# BDCMC_H-Bridge_24V50A.net
KiCad netlist of a schematic drawn in EAGLE
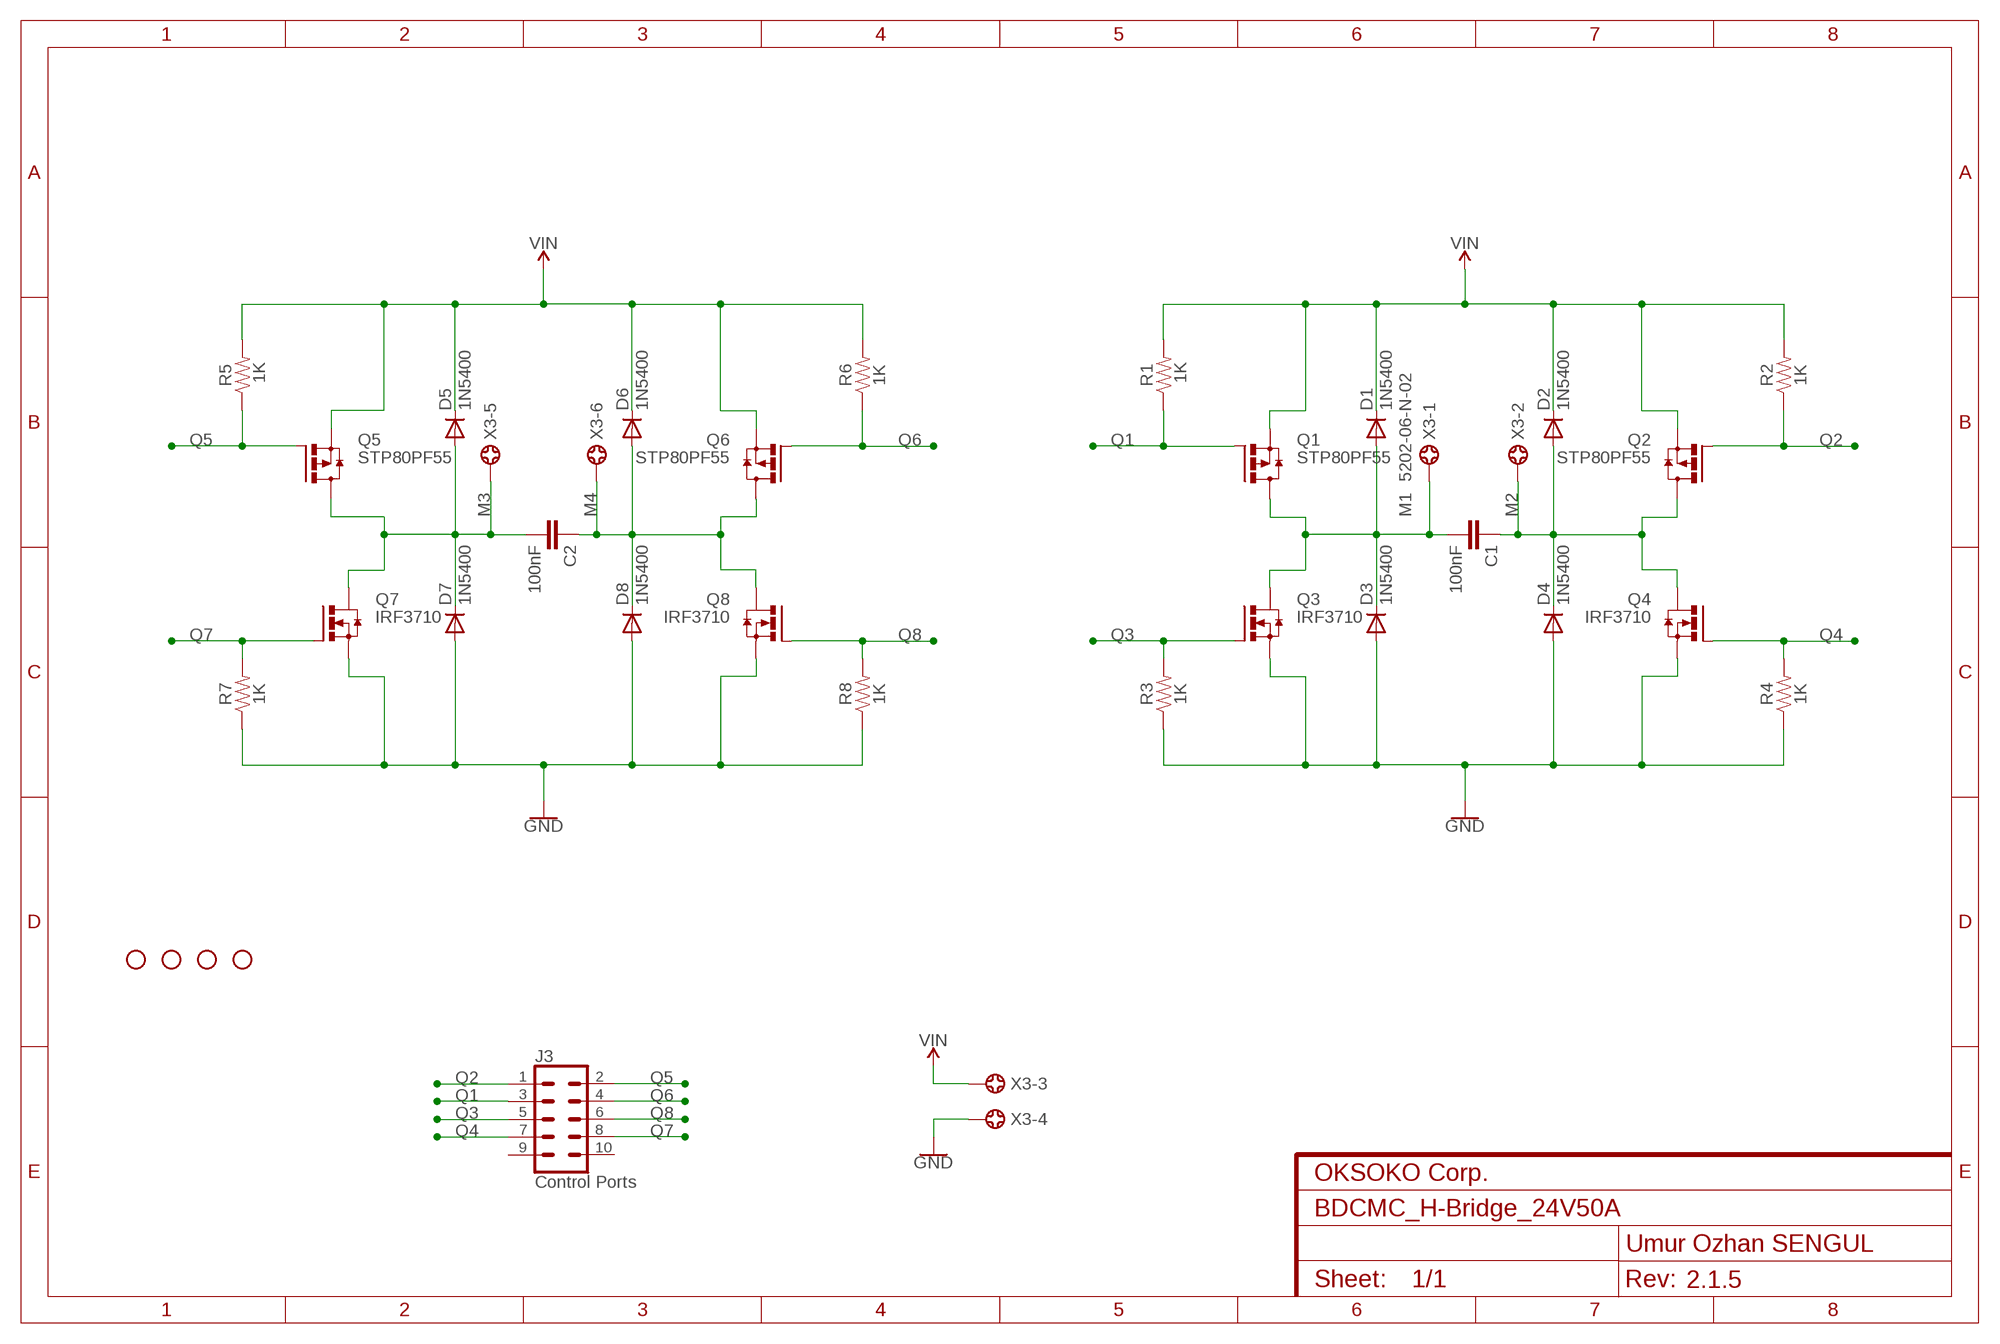
[diagram p0: schematic, sheet 1]

(export (version "E")
  (design (tool "Eeschema 10.0.6"))
  (components
    (comp (ref "C1")
      (value "100nF")
      (footprint "eagle-import:CAP-PTH-2.54")
      (libsource (lib "eagle-import") (part "22PF-PTH-2.54MM-200V-5%"))
    )
    (comp (ref "C2")
      (value "100nF")
      (footprint "eagle-import:CAP-PTH-2.54")
      (libsource (lib "eagle-import") (part "22PF-PTH-2.54MM-200V-5%"))
    )
    (comp (ref "D1")
      (value "1N5400")
      (footprint "eagle-import:DO201-15")
      (libsource (lib "eagle-import") (part "1N5400"))
    )
    (comp (ref "D2")
      (value "1N5400")
      (footprint "eagle-import:DO201-15")
      (libsource (lib "eagle-import") (part "1N5400"))
    )
    (comp (ref "D3")
      (value "1N5400")
      (footprint "eagle-import:DO201-15")
      (libsource (lib "eagle-import") (part "1N5400"))
    )
    (comp (ref "D4")
      (value "1N5400")
      (footprint "eagle-import:DO201-15")
      (libsource (lib "eagle-import") (part "1N5400"))
    )
    (comp (ref "D5")
      (value "1N5400")
      (footprint "eagle-import:DO201-15")
      (libsource (lib "eagle-import") (part "1N5400"))
    )
    (comp (ref "D6")
      (value "1N5400")
      (footprint "eagle-import:DO201-15")
      (libsource (lib "eagle-import") (part "1N5400"))
    )
    (comp (ref "D7")
      (value "1N5400")
      (footprint "eagle-import:DO201-15")
      (libsource (lib "eagle-import") (part "1N5400"))
    )
    (comp (ref "D8")
      (value "1N5400")
      (footprint "eagle-import:DO201-15")
      (libsource (lib "eagle-import") (part "1N5400"))
    )
    (comp (ref "H1")
      (value "STAND-OFF")
      (footprint "eagle-import:STAND-OFF")
      (libsource (lib "eagle-import") (part "STAND-OFF"))
    )
    (comp (ref "H2")
      (value "STAND-OFF")
      (footprint "eagle-import:STAND-OFF")
      (libsource (lib "eagle-import") (part "STAND-OFF"))
    )
    (comp (ref "H3")
      (value "STAND-OFF")
      (footprint "eagle-import:STAND-OFF")
      (libsource (lib "eagle-import") (part "STAND-OFF"))
    )
    (comp (ref "H4")
      (value "STAND-OFF")
      (footprint "eagle-import:STAND-OFF")
      (libsource (lib "eagle-import") (part "STAND-OFF"))
    )
    (comp (ref "J3")
      (value "Control Ports")
      (footprint "eagle-import:2X5-SHROUDED")
      (libsource (lib "eagle-import") (part "CONN_05X2SHD"))
    )
    (comp (ref "Q1")
      (value "STP80PF55")
      (footprint "eagle-import:TO220")
      (libsource (lib "eagle-import") (part "STP80PF55"))
    )
    (comp (ref "Q2")
      (value "STP80PF55")
      (footprint "eagle-import:TO220")
      (libsource (lib "eagle-import") (part "STP80PF55"))
    )
    (comp (ref "Q3")
      (value "IRF3710")
      (footprint "eagle-import:TO220BH")
      (libsource (lib "eagle-import") (part "IRF3710"))
    )
    (comp (ref "Q4")
      (value "IRF3710")
      (footprint "eagle-import:TO220BH")
      (libsource (lib "eagle-import") (part "IRF3710"))
    )
    (comp (ref "Q5")
      (value "STP80PF55")
      (footprint "eagle-import:TO220")
      (libsource (lib "eagle-import") (part "STP80PF55"))
    )
    (comp (ref "Q6")
      (value "STP80PF55")
      (footprint "eagle-import:TO220")
      (libsource (lib "eagle-import") (part "STP80PF55"))
    )
    (comp (ref "Q7")
      (value "IRF3710")
      (footprint "eagle-import:TO220BH")
      (libsource (lib "eagle-import") (part "IRF3710"))
    )
    (comp (ref "Q8")
      (value "IRF3710")
      (footprint "eagle-import:TO220BH")
      (libsource (lib "eagle-import") (part "IRF3710"))
    )
    (comp (ref "R1")
      (value "1K")
      (footprint "eagle-import:AXIAL-0.3")
      (libsource (lib "eagle-import") (part "RESISTORAXIAL-0.3"))
    )
    (comp (ref "R2")
      (value "1K")
      (footprint "eagle-import:AXIAL-0.3")
      (libsource (lib "eagle-import") (part "RESISTORAXIAL-0.3"))
    )
    (comp (ref "R3")
      (value "1K")
      (footprint "eagle-import:AXIAL-0.3")
      (libsource (lib "eagle-import") (part "RESISTORAXIAL-0.3"))
    )
    (comp (ref "R4")
      (value "1K")
      (footprint "eagle-import:AXIAL-0.3")
      (libsource (lib "eagle-import") (part "RESISTORAXIAL-0.3"))
    )
    (comp (ref "R5")
      (value "1K")
      (footprint "eagle-import:AXIAL-0.3")
      (libsource (lib "eagle-import") (part "RESISTORAXIAL-0.3"))
    )
    (comp (ref "R6")
      (value "1K")
      (footprint "eagle-import:AXIAL-0.3")
      (libsource (lib "eagle-import") (part "RESISTORAXIAL-0.3"))
    )
    (comp (ref "R7")
      (value "1K")
      (footprint "eagle-import:AXIAL-0.3")
      (libsource (lib "eagle-import") (part "RESISTORAXIAL-0.3"))
    )
    (comp (ref "R8")
      (value "1K")
      (footprint "eagle-import:AXIAL-0.3")
      (libsource (lib "eagle-import") (part "RESISTORAXIAL-0.3"))
    )
    (comp (ref "X3")
      (value "5202-06-N-02")
      (footprint "eagle-import:5202-06-N-02")
      (libsource (lib "eagle-import") (part "5202-06-N-02"))
    )
  )
  (nets
    (net (code "1") (name "/M1") (class "Default")
      (node (ref "C1") (pin "2") (pinfunction "2_2") (pintype "passive"))
      (node (ref "D1") (pin "A") (pinfunction "A_A") (pintype "passive"))
      (node (ref "D3") (pin "C") (pinfunction "C_C") (pintype "passive"))
      (node (ref "Q1") (pin "D") (pinfunction "D_D") (pintype "passive"))
      (node (ref "Q3") (pin "D") (pinfunction "D_D") (pintype "passive"))
      (node (ref "X3") (pin "1") (pinfunction "1_1") (pintype "passive"))
    )
    (net (code "2") (name "/M2") (class "Default")
      (node (ref "C1") (pin "1") (pinfunction "1_1") (pintype "passive"))
      (node (ref "D2") (pin "A") (pinfunction "A_A") (pintype "passive"))
      (node (ref "D4") (pin "C") (pinfunction "C_C") (pintype "passive"))
      (node (ref "Q2") (pin "D") (pinfunction "D_D") (pintype "passive"))
      (node (ref "Q4") (pin "D") (pinfunction "D_D") (pintype "passive"))
      (node (ref "X3") (pin "2") (pinfunction "1_2") (pintype "passive"))
    )
    (net (code "3") (name "/M3") (class "Default")
      (node (ref "C2") (pin "2") (pinfunction "2_2") (pintype "passive"))
      (node (ref "D5") (pin "A") (pinfunction "A_A") (pintype "passive"))
      (node (ref "D7") (pin "C") (pinfunction "C_C") (pintype "passive"))
      (node (ref "Q5") (pin "D") (pinfunction "D_D") (pintype "passive"))
      (node (ref "Q7") (pin "D") (pinfunction "D_D") (pintype "passive"))
      (node (ref "X3") (pin "5") (pinfunction "1_5") (pintype "passive"))
    )
    (net (code "4") (name "/M4") (class "Default")
      (node (ref "C2") (pin "1") (pinfunction "1_1") (pintype "passive"))
      (node (ref "D6") (pin "A") (pinfunction "A_A") (pintype "passive"))
      (node (ref "D8") (pin "C") (pinfunction "C_C") (pintype "passive"))
      (node (ref "Q6") (pin "D") (pinfunction "D_D") (pintype "passive"))
      (node (ref "Q8") (pin "D") (pinfunction "D_D") (pintype "passive"))
      (node (ref "X3") (pin "6") (pinfunction "1_6") (pintype "passive"))
    )
    (net (code "5") (name "/Q1") (class "Default")
      (node (ref "J3") (pin "3") (pinfunction "3_3") (pintype "passive"))
      (node (ref "Q1") (pin "G") (pinfunction "G_G") (pintype "passive"))
      (node (ref "R1") (pin "P$1") (pinfunction "1_P$1") (pintype "passive"))
    )
    (net (code "6") (name "/Q2") (class "Default")
      (node (ref "J3") (pin "1") (pinfunction "1_1") (pintype "passive"))
      (node (ref "Q2") (pin "G") (pinfunction "G_G") (pintype "passive"))
      (node (ref "R2") (pin "P$1") (pinfunction "1_P$1") (pintype "passive"))
    )
    (net (code "7") (name "/Q3") (class "Default")
      (node (ref "J3") (pin "5") (pinfunction "5_5") (pintype "passive"))
      (node (ref "Q3") (pin "G") (pinfunction "G_G") (pintype "passive"))
      (node (ref "R3") (pin "P$2") (pinfunction "2_P$2") (pintype "passive"))
    )
    (net (code "8") (name "/Q4") (class "Default")
      (node (ref "J3") (pin "7") (pinfunction "7_7") (pintype "passive"))
      (node (ref "Q4") (pin "G") (pinfunction "G_G") (pintype "passive"))
      (node (ref "R4") (pin "P$2") (pinfunction "2_P$2") (pintype "passive"))
    )
    (net (code "9") (name "/Q5") (class "Default")
      (node (ref "J3") (pin "2") (pinfunction "2_2") (pintype "passive"))
      (node (ref "Q5") (pin "G") (pinfunction "G_G") (pintype "passive"))
      (node (ref "R5") (pin "P$1") (pinfunction "1_P$1") (pintype "passive"))
    )
    (net (code "10") (name "/Q6") (class "Default")
      (node (ref "J3") (pin "4") (pinfunction "4_4") (pintype "passive"))
      (node (ref "Q6") (pin "G") (pinfunction "G_G") (pintype "passive"))
      (node (ref "R6") (pin "P$1") (pinfunction "1_P$1") (pintype "passive"))
    )
    (net (code "11") (name "/Q7") (class "Default")
      (node (ref "J3") (pin "8") (pinfunction "8_8") (pintype "passive"))
      (node (ref "Q7") (pin "G") (pinfunction "G_G") (pintype "passive"))
      (node (ref "R7") (pin "P$2") (pinfunction "2_P$2") (pintype "passive"))
    )
    (net (code "12") (name "/Q8") (class "Default")
      (node (ref "J3") (pin "6") (pinfunction "6_6") (pintype "passive"))
      (node (ref "Q8") (pin "G") (pinfunction "G_G") (pintype "passive"))
      (node (ref "R8") (pin "P$2") (pinfunction "2_P$2") (pintype "passive"))
    )
    (net (code "13") (name "GND") (class "Default")
      (node (ref "D3") (pin "A") (pinfunction "A_A") (pintype "passive"))
      (node (ref "D4") (pin "A") (pinfunction "A_A") (pintype "passive"))
      (node (ref "D7") (pin "A") (pinfunction "A_A") (pintype "passive"))
      (node (ref "D8") (pin "A") (pinfunction "A_A") (pintype "passive"))
      (node (ref "Q3") (pin "S") (pinfunction "S_S") (pintype "passive"))
      (node (ref "Q4") (pin "S") (pinfunction "S_S") (pintype "passive"))
      (node (ref "Q7") (pin "S") (pinfunction "S_S") (pintype "passive"))
      (node (ref "Q8") (pin "S") (pinfunction "S_S") (pintype "passive"))
      (node (ref "R3") (pin "P$1") (pinfunction "1_P$1") (pintype "passive"))
      (node (ref "R4") (pin "P$1") (pinfunction "1_P$1") (pintype "passive"))
      (node (ref "R7") (pin "P$1") (pinfunction "1_P$1") (pintype "passive"))
      (node (ref "R8") (pin "P$1") (pinfunction "1_P$1") (pintype "passive"))
      (node (ref "X3") (pin "4") (pinfunction "1_4") (pintype "passive"))
    )
    (net (code "14") (name "VIN") (class "Default")
      (node (ref "D1") (pin "C") (pinfunction "C_C") (pintype "passive"))
      (node (ref "D2") (pin "C") (pinfunction "C_C") (pintype "passive"))
      (node (ref "D5") (pin "C") (pinfunction "C_C") (pintype "passive"))
      (node (ref "D6") (pin "C") (pinfunction "C_C") (pintype "passive"))
      (node (ref "Q1") (pin "S") (pinfunction "S_S") (pintype "passive"))
      (node (ref "Q2") (pin "S") (pinfunction "S_S") (pintype "passive"))
      (node (ref "Q5") (pin "S") (pinfunction "S_S") (pintype "passive"))
      (node (ref "Q6") (pin "S") (pinfunction "S_S") (pintype "passive"))
      (node (ref "R1") (pin "P$2") (pinfunction "2_P$2") (pintype "passive"))
      (node (ref "R2") (pin "P$2") (pinfunction "2_P$2") (pintype "passive"))
      (node (ref "R5") (pin "P$2") (pinfunction "2_P$2") (pintype "passive"))
      (node (ref "R6") (pin "P$2") (pinfunction "2_P$2") (pintype "passive"))
      (node (ref "X3") (pin "3") (pinfunction "1_3") (pintype "passive"))
    )
    (net (code "15") (name "unconnected-(J3-Pad9)") (class "Default")
      (node (ref "J3") (pin "9") (pinfunction "9_9") (pintype "passive"))
    )
    (net (code "16") (name "unconnected-(J3-Pad10)") (class "Default")
      (node (ref "J3") (pin "10") (pinfunction "10_10") (pintype "passive"))
    )
  )
)
